# Connectors.net
KiCad netlist of a schematic drawn in Altium Designer
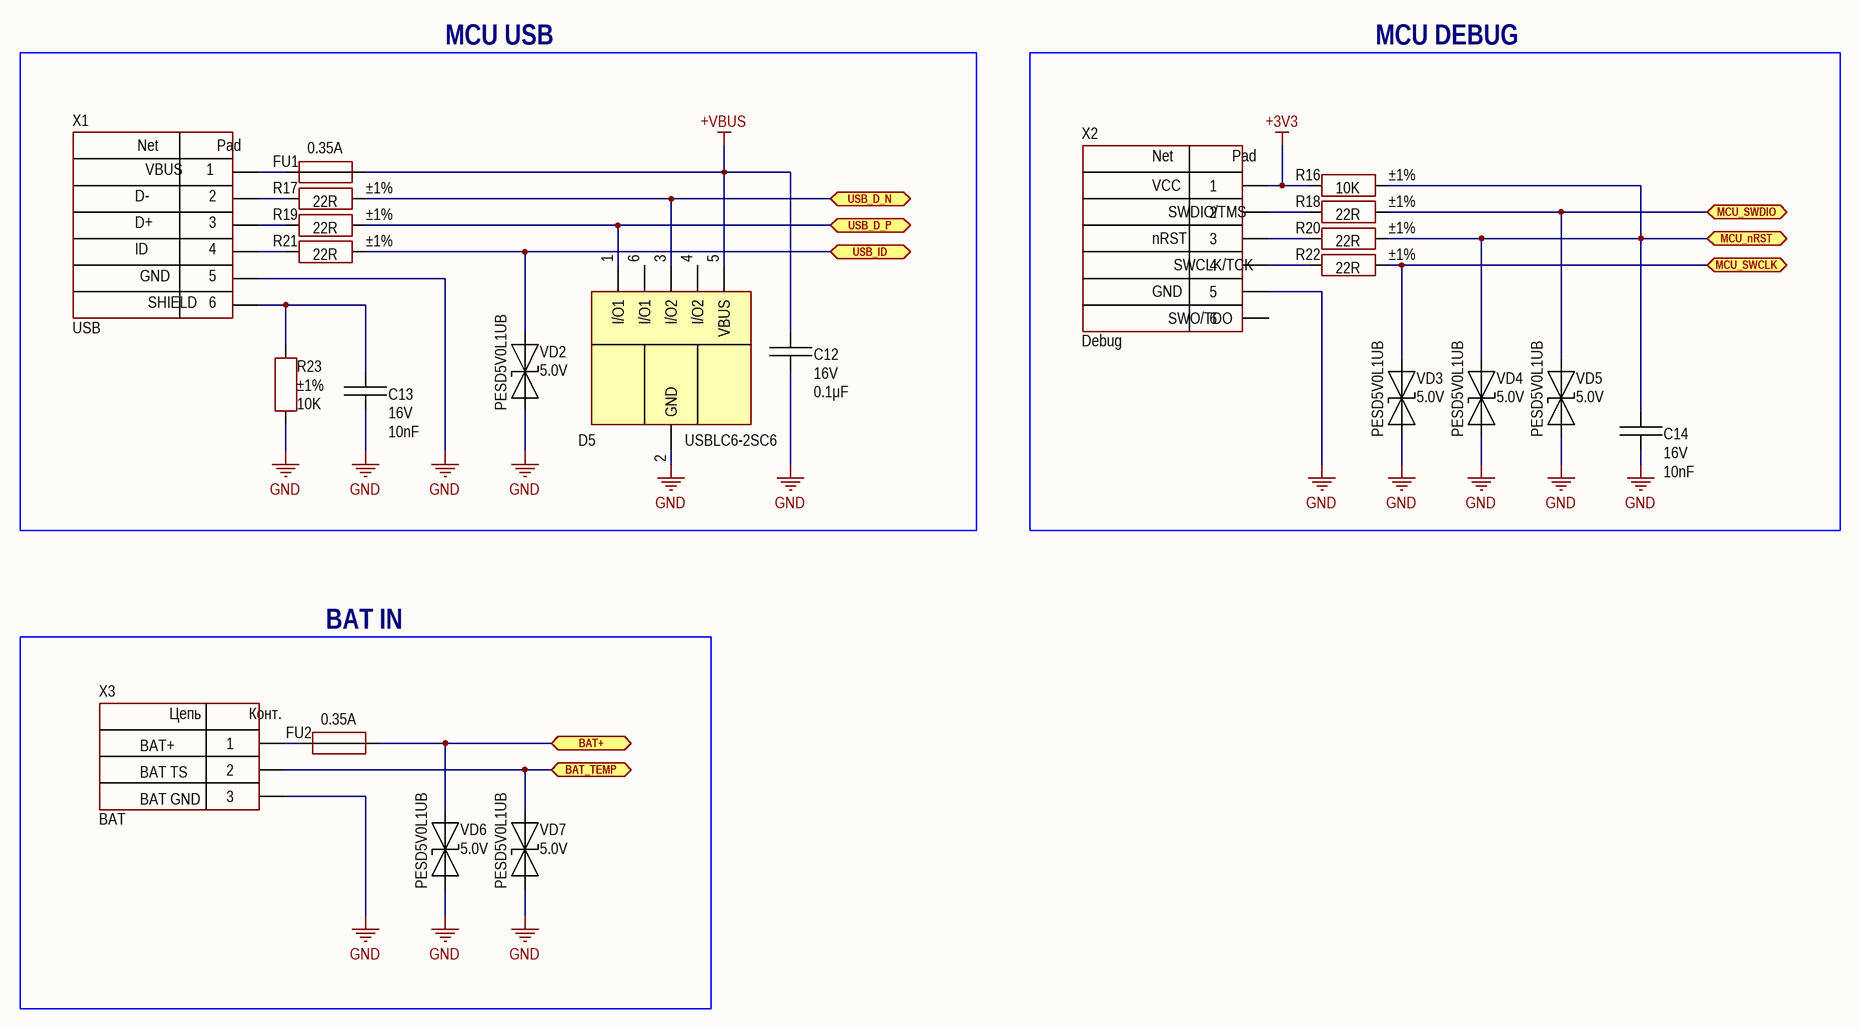
[diagram p0: Connectors.SchDoc]

(export (version "E")
  (design (tool "Eeschema 10.0.6"))
  (components
    (comp (ref "C12")
      (value "0.1μF")
      (footprint "CAP: 0402_NO_SILK")
      (description "0.1 µF ±10% 16V Ceramic Capacitor X7R 0402 (1005 Metric)")
      (fields
        (field (name "MANUFACTURER") "Yageo")
        (field (name "PARTNUMBER") "CC0402KRX7R7BB104")
        (field (name "VOLTAGE") "16V")
      )
      (libsource (lib "capacitor") (part "Ceramic_0402"))
    )
    (comp (ref "C13")
      (value "10nF")
      (footprint "CAP: 0201")
      (description "10000 pF ±10% 16V Ceramic Capacitor X7R 0201 (0603 Metric)")
      (fields
        (field (name "MANUFACTURER") "Yageo")
        (field (name "PARTNUMBER") "CC0201KRX7R7BB103")
        (field (name "VOLTAGE") "16V")
      )
      (libsource (lib "capacitor") (part "Ceramic_0201"))
    )
    (comp (ref "C14")
      (value "10nF")
      (footprint "CAP: 0201")
      (description "10000 pF ±10% 16V Ceramic Capacitor X7R 0201 (0603 Metric)")
      (fields
        (field (name "MANUFACTURER") "Yageo")
        (field (name "PARTNUMBER") "CC0201KRX7R7BB103")
        (field (name "VOLTAGE") "16V")
      )
      (libsource (lib "capacitor") (part "Ceramic_0201"))
    )
    (comp (ref "D5")
      (value "~")
      (footprint "SOT23-6")
      (description "ESD diode array")
      (fields
        (field (name "MANUFACTURER") "STMicroelectronics")
        (field (name "VALUEMANUFACTURERPARTNUMBER") "USB protection, , 5A peak, 17V, Power line, SOT-23-6, -40...+125°C")
        (field (name "PARTNUMBER") "USBLC6-2SC6")
      )
      (libsource (lib "MyLib") (part "USBLC6-2SC6"))
    )
    (comp (ref "FU1")
      (value "~")
      (footprint "FUSE 0402")
      (description "Polymeric PTC Resettable Fuse 6V 350 mA Ih Surface Mount 0402 (1005 Metric), Concave")
      (fields
        (field (name "MANUFACTURER") "Bourns")
        (field (name "VALUEMANUFACTURERPARTNUMBER") "PTC, 250VAC, 0.35A, 0402, ")
        (field (name "MAXCURRENT") "0.35A")
      )
      (libsource (lib "electromechanics") (part "Fuse"))
    )
    (comp (ref "FU2")
      (value "~")
      (footprint "FUSE 0402")
      (description "Polymeric PTC Resettable Fuse 6V 350 mA Ih Surface Mount 0402 (1005 Metric), Concave")
      (fields
        (field (name "MANUFACTURER") "Bourns")
        (field (name "VALUEMANUFACTURERPARTNUMBER") "PTC, 250VAC, 0.35A, 0402, ")
        (field (name "MAXCURRENT") "0.35A")
      )
      (libsource (lib "electromechanics") (part "Fuse"))
    )
    (comp (ref "R16")
      (value "10K")
      (footprint "RES: 0201")
      (description "10 kOhms ±1% 0.05W, 1/20W Chip Resistor 0201 (0603 Metric) Moisture Resistant Thick Film")
      (fields
        (field (name "MANUFACTURER") "Yageo")
        (field (name "PARTNUMBER") "RC0201JR-0710KL")
        (field (name "TOLERANCE") "±1%")
      )
      (libsource (lib "") (part "Resistor_0201_1"))
    )
    (comp (ref "R17")
      (value "22R")
      (footprint "RES: 0201")
      (description "22 Ohms ±1% 0.05W, 1/20W Chip Resistor 0201 (0603 Metric) Moisture Resistant Thick Film")
      (fields
        (field (name "MANUFACTURER") "Yageo")
        (field (name "PARTNUMBER") "RC0201FR-0722RL")
        (field (name "TOLERANCE") "±1%")
      )
      (libsource (lib "resistor") (part "Resistor_0201"))
    )
    (comp (ref "R18")
      (value "22R")
      (footprint "RES: 0201")
      (description "22 Ohms ±1% 0.05W, 1/20W Chip Resistor 0201 (0603 Metric) Moisture Resistant Thick Film")
      (fields
        (field (name "MANUFACTURER") "Yageo")
        (field (name "PARTNUMBER") "RC0201FR-0722RL")
        (field (name "TOLERANCE") "±1%")
      )
      (libsource (lib "resistor") (part "Resistor_0201"))
    )
    (comp (ref "R19")
      (value "22R")
      (footprint "RES: 0201")
      (description "22 Ohms ±1% 0.05W, 1/20W Chip Resistor 0201 (0603 Metric) Moisture Resistant Thick Film")
      (fields
        (field (name "MANUFACTURER") "Yageo")
        (field (name "PARTNUMBER") "RC0201FR-0722RL")
        (field (name "TOLERANCE") "±1%")
      )
      (libsource (lib "resistor") (part "Resistor_0201"))
    )
    (comp (ref "R20")
      (value "22R")
      (footprint "RES: 0201")
      (description "22 Ohms ±1% 0.05W, 1/20W Chip Resistor 0201 (0603 Metric) Moisture Resistant Thick Film")
      (fields
        (field (name "MANUFACTURER") "Yageo")
        (field (name "PARTNUMBER") "RC0201FR-0722RL")
        (field (name "TOLERANCE") "±1%")
      )
      (libsource (lib "resistor") (part "Resistor_0201"))
    )
    (comp (ref "R21")
      (value "22R")
      (footprint "RES: 0201")
      (description "22 Ohms ±1% 0.05W, 1/20W Chip Resistor 0201 (0603 Metric) Moisture Resistant Thick Film")
      (fields
        (field (name "MANUFACTURER") "Yageo")
        (field (name "PARTNUMBER") "RC0201FR-0722RL")
        (field (name "TOLERANCE") "±1%")
      )
      (libsource (lib "resistor") (part "Resistor_0201"))
    )
    (comp (ref "R22")
      (value "22R")
      (footprint "RES: 0201")
      (description "22 Ohms ±1% 0.05W, 1/20W Chip Resistor 0201 (0603 Metric) Moisture Resistant Thick Film")
      (fields
        (field (name "MANUFACTURER") "Yageo")
        (field (name "PARTNUMBER") "RC0201FR-0722RL")
        (field (name "TOLERANCE") "±1%")
      )
      (libsource (lib "resistor") (part "Resistor_0201"))
    )
    (comp (ref "R23")
      (value "10K")
      (footprint "RES: 0201")
      (description "10 kOhms ±1% 0.05W, 1/20W Chip Resistor 0201 (0603 Metric) Moisture Resistant Thick Film")
      (fields
        (field (name "MANUFACTURER") "Yageo")
        (field (name "PARTNUMBER") "RC0201JR-0710KL")
        (field (name "TOLERANCE") "±1%")
      )
      (libsource (lib "resistor") (part "Resistor_0201"))
    )
    (comp (ref "VD2")
      (value "~")
      (footprint "DIODE: SOD523")
      (description "12V Clamp 3.5A (8/20µs) Ipp Tvs Diode Surface Mount SOD-523")
      (fields
        (field (name "MANUFACTURER") "Nexperia")
        (field (name "VALUEMANUFACTURERPARTNUMBER") "ESD TVS diode, 5.0V, 3.5A, , , SOD-523, -55...+150°C")
        (field (name "VOLTAGE") "5.0V")
        (field (name "PARTNUMBER") "PESD5V0L1UB")
      )
      (libsource (lib "diode") (part "TVS_single"))
    )
    (comp (ref "VD3")
      (value "~")
      (footprint "DIODE: SOD523")
      (description "12V Clamp 3.5A (8/20µs) Ipp Tvs Diode Surface Mount SOD-523")
      (fields
        (field (name "MANUFACTURER") "Nexperia")
        (field (name "VALUEMANUFACTURERPARTNUMBER") "ESD TVS diode, 5.0V, 3.5A, , , SOD-523, -55...+150°C")
        (field (name "VOLTAGE") "5.0V")
        (field (name "PARTNUMBER") "PESD5V0L1UB")
      )
      (libsource (lib "diode") (part "TVS_single"))
    )
    (comp (ref "VD4")
      (value "~")
      (footprint "DIODE: SOD523")
      (description "12V Clamp 3.5A (8/20µs) Ipp Tvs Diode Surface Mount SOD-523")
      (fields
        (field (name "MANUFACTURER") "Nexperia")
        (field (name "VALUEMANUFACTURERPARTNUMBER") "ESD TVS diode, 5.0V, 3.5A, , , SOD-523, -55...+150°C")
        (field (name "VOLTAGE") "5.0V")
        (field (name "PARTNUMBER") "PESD5V0L1UB")
      )
      (libsource (lib "diode") (part "TVS_single"))
    )
    (comp (ref "VD5")
      (value "~")
      (footprint "DIODE: SOD523")
      (description "12V Clamp 3.5A (8/20µs) Ipp Tvs Diode Surface Mount SOD-523")
      (fields
        (field (name "MANUFACTURER") "Nexperia")
        (field (name "VALUEMANUFACTURERPARTNUMBER") "ESD TVS diode, 5.0V, 3.5A, , , SOD-523, -55...+150°C")
        (field (name "VOLTAGE") "5.0V")
        (field (name "PARTNUMBER") "PESD5V0L1UB")
      )
      (libsource (lib "diode") (part "TVS_single"))
    )
    (comp (ref "VD6")
      (value "~")
      (footprint "DIODE: SOD523")
      (description "12V Clamp 3.5A (8/20µs) Ipp Tvs Diode Surface Mount SOD-523")
      (fields
        (field (name "MANUFACTURER") "Nexperia")
        (field (name "VALUEMANUFACTURERPARTNUMBER") "ESD TVS diode, 5.0V, 3.5A, , , SOD-523, -55...+150°C")
        (field (name "VOLTAGE") "5.0V")
        (field (name "PARTNUMBER") "PESD5V0L1UB")
      )
      (libsource (lib "diode") (part "TVS_single"))
    )
    (comp (ref "VD7")
      (value "~")
      (footprint "DIODE: SOD523")
      (description "12V Clamp 3.5A (8/20µs) Ipp Tvs Diode Surface Mount SOD-523")
      (fields
        (field (name "MANUFACTURER") "Nexperia")
        (field (name "VALUEMANUFACTURERPARTNUMBER") "ESD TVS diode, 5.0V, 3.5A, , , SOD-523, -55...+150°C")
        (field (name "VOLTAGE") "5.0V")
        (field (name "PARTNUMBER") "PESD5V0L1UB")
      )
      (libsource (lib "diode") (part "TVS_single"))
    )
    (comp (ref "X1")
      (value "~")
      (footprint "CON: USB micro-A (ZX62-B-5PA)")
      (description "USB-micro")
      (fields
        (field (name "MANUFACTURER") "Hirose Electric")
        (field (name "VALUEMANUFACTURERPARTNUMBER") "USB micro B")
        (field (name "COMMENTTEXT") "USB")
      )
      (libsource (lib "MyLib") (part "Connector_USB_micro_B"))
    )
    (comp (ref "X2")
      (value "~")
      (footprint "CON: TC2030-IDC-NL")
      (description "Tag-connect TC2030-IDC-NL debug footprint")
      (fields
        (field (name "MANUFACTURER") "Tag-Connect")
        (field (name "VALUEMANUFACTURERPARTNUMBER") "Debug connector, 6pin, , , ")
        (field (name "COMMENTTEXT") "Debug")
      )
      (libsource (lib "MyLib") (part "TC2030-IDC-NL"))
    )
    (comp (ref "X3")
      (value "~")
      (footprint "CON: WF-03")
      (fields
        (field (name "MANUFACTURER") "Connfly")
        (field (name "VALUEMANUFACTURERPARTNUMBER") "Connector, 3pin, 2.54mm, 250VAC, 3A")
        (field (name "PARTNUMBER") "WF-3")
        (field (name "COMMENTTEXT") "BAT")
      )
      (libsource (lib "connector") (part "WF-3"))
    )
  )
  (nets
    (net (code "1") (name "+3V3") (class "Default")
      (node (ref "R16") (pin "2") (pinfunction "2_2") (pintype "passive"))
      (node (ref "X2") (pin "1") (pinfunction "1_1") (pintype "passive"))
    )
    (net (code "2") (name "+VBUS") (class "Default")
      (node (ref "C12") (pin "2") (pinfunction "2_2") (pintype "passive"))
      (node (ref "D5") (pin "5") (pinfunction "VBUS_5") (pintype "passive"))
      (node (ref "FU1") (pin "2") (pinfunction "2_2") (pintype "passive"))
    )
    (net (code "3") (name "/BAT+") (class "Default")
      (node (ref "FU2") (pin "2") (pinfunction "2_2") (pintype "passive"))
      (node (ref "VD6") (pin "2") (pinfunction "C_2") (pintype "passive"))
    )
    (net (code "4") (name "/BAT_TEMP") (class "Default")
      (node (ref "VD7") (pin "2") (pinfunction "C_2") (pintype "passive"))
      (node (ref "X3") (pin "2") (pinfunction "2_2") (pintype "passive"))
    )
    (net (code "5") (name "/MCU_SWCLK") (class "Default")
      (node (ref "R22") (pin "2") (pinfunction "2_2") (pintype "passive"))
      (node (ref "VD3") (pin "2") (pinfunction "C_2") (pintype "passive"))
    )
    (net (code "6") (name "/MCU_SWDIO") (class "Default")
      (node (ref "R18") (pin "2") (pinfunction "2_2") (pintype "passive"))
      (node (ref "VD5") (pin "2") (pinfunction "C_2") (pintype "passive"))
    )
    (net (code "7") (name "/MCU_nRST") (class "Default")
      (node (ref "C14") (pin "2") (pinfunction "2_2") (pintype "passive"))
      (node (ref "R16") (pin "1") (pinfunction "1_1") (pintype "passive"))
      (node (ref "R20") (pin "2") (pinfunction "2_2") (pintype "passive"))
      (node (ref "VD4") (pin "2") (pinfunction "C_2") (pintype "passive"))
    )
    (net (code "8") (name "/USB_D_N") (class "Default")
      (node (ref "D5") (pin "3") (pinfunction "I/O2_3") (pintype "passive"))
      (node (ref "R17") (pin "2") (pinfunction "2_2") (pintype "passive"))
    )
    (net (code "9") (name "/USB_D_P") (class "Default")
      (node (ref "D5") (pin "1") (pinfunction "I/O1_1") (pintype "passive"))
      (node (ref "R19") (pin "2") (pinfunction "2_2") (pintype "passive"))
    )
    (net (code "10") (name "/USB_ID") (class "Default")
      (node (ref "R21") (pin "2") (pinfunction "2_2") (pintype "passive"))
      (node (ref "VD2") (pin "2") (pinfunction "C_2") (pintype "passive"))
    )
    (net (code "11") (name "GND") (class "Default")
      (node (ref "C12") (pin "1") (pinfunction "1_1") (pintype "passive"))
      (node (ref "C13") (pin "1") (pinfunction "1_1") (pintype "passive"))
      (node (ref "C14") (pin "1") (pinfunction "1_1") (pintype "passive"))
      (node (ref "D5") (pin "2") (pinfunction "GND_2") (pintype "passive"))
      (node (ref "R23") (pin "1") (pinfunction "1_1") (pintype "passive"))
      (node (ref "VD2") (pin "1") (pinfunction "A_1") (pintype "passive"))
      (node (ref "VD3") (pin "1") (pinfunction "A_1") (pintype "passive"))
      (node (ref "VD4") (pin "1") (pinfunction "A_1") (pintype "passive"))
      (node (ref "VD5") (pin "1") (pinfunction "A_1") (pintype "passive"))
      (node (ref "VD6") (pin "1") (pinfunction "A_1") (pintype "passive"))
      (node (ref "VD7") (pin "1") (pinfunction "A_1") (pintype "passive"))
      (node (ref "X1") (pin "5") (pinfunction "5_5") (pintype "passive"))
      (node (ref "X2") (pin "5") (pinfunction "5_5") (pintype "passive"))
      (node (ref "X3") (pin "3") (pinfunction "3_3") (pintype "power_in"))
    )
    (net (code "12") (name "Net-(C13-Pad2)") (class "Default")
      (node (ref "C13") (pin "2") (pinfunction "2_2") (pintype "passive"))
      (node (ref "R23") (pin "2") (pinfunction "2_2") (pintype "passive"))
      (node (ref "X1") (pin "0") (pinfunction "0_0") (pintype "passive"))
    )
    (net (code "13") (name "Net-(FU1-Pad1)") (class "Default")
      (node (ref "FU1") (pin "1") (pinfunction "1_1") (pintype "passive"))
      (node (ref "X1") (pin "1") (pintype "passive"))
    )
    (net (code "14") (name "Net-(FU2-Pad1)") (class "Default")
      (node (ref "FU2") (pin "1") (pinfunction "1_1") (pintype "passive"))
      (node (ref "X3") (pin "1") (pinfunction "1_1") (pintype "passive"))
    )
    (net (code "15") (name "Net-(R17-Pad1)") (class "Default")
      (node (ref "R17") (pin "1") (pinfunction "1_1") (pintype "passive"))
      (node (ref "X1") (pin "2") (pinfunction "2_2") (pintype "passive"))
    )
    (net (code "16") (name "Net-(R18-Pad1)") (class "Default")
      (node (ref "R18") (pin "1") (pinfunction "1_1") (pintype "passive"))
      (node (ref "X2") (pin "2") (pinfunction "2_2") (pintype "passive"))
    )
    (net (code "17") (name "Net-(R19-Pad1)") (class "Default")
      (node (ref "R19") (pin "1") (pinfunction "1_1") (pintype "passive"))
      (node (ref "X1") (pin "3") (pinfunction "3_3") (pintype "passive"))
    )
    (net (code "18") (name "Net-(R20-Pad1)") (class "Default")
      (node (ref "R20") (pin "1") (pinfunction "1_1") (pintype "passive"))
      (node (ref "X2") (pin "3") (pinfunction "3_3") (pintype "passive"))
    )
    (net (code "19") (name "Net-(R21-Pad1)") (class "Default")
      (node (ref "R21") (pin "1") (pinfunction "1_1") (pintype "passive"))
      (node (ref "X1") (pin "4") (pinfunction "4_4") (pintype "passive"))
    )
    (net (code "20") (name "Net-(R22-Pad1)") (class "Default")
      (node (ref "R22") (pin "1") (pinfunction "1_1") (pintype "passive"))
      (node (ref "X2") (pin "4") (pinfunction "4_4") (pintype "passive"))
    )
    (net (code "21") (name "unconnected-(D5-I{slash}O1-Pad6)") (class "Default")
      (node (ref "D5") (pin "6") (pinfunction "I/O1_6") (pintype "passive"))
    )
    (net (code "22") (name "unconnected-(D5-I{slash}O2-Pad4)") (class "Default")
      (node (ref "D5") (pin "4") (pinfunction "I/O2_4") (pintype "passive"))
    )
    (net (code "23") (name "unconnected-(X2-Pad6)") (class "Default")
      (node (ref "X2") (pin "6") (pinfunction "6_6") (pintype "passive"))
    )
  )
)
